# RECEIVER_IC.net
KiCad netlist of a schematic drawn in Altium Designer
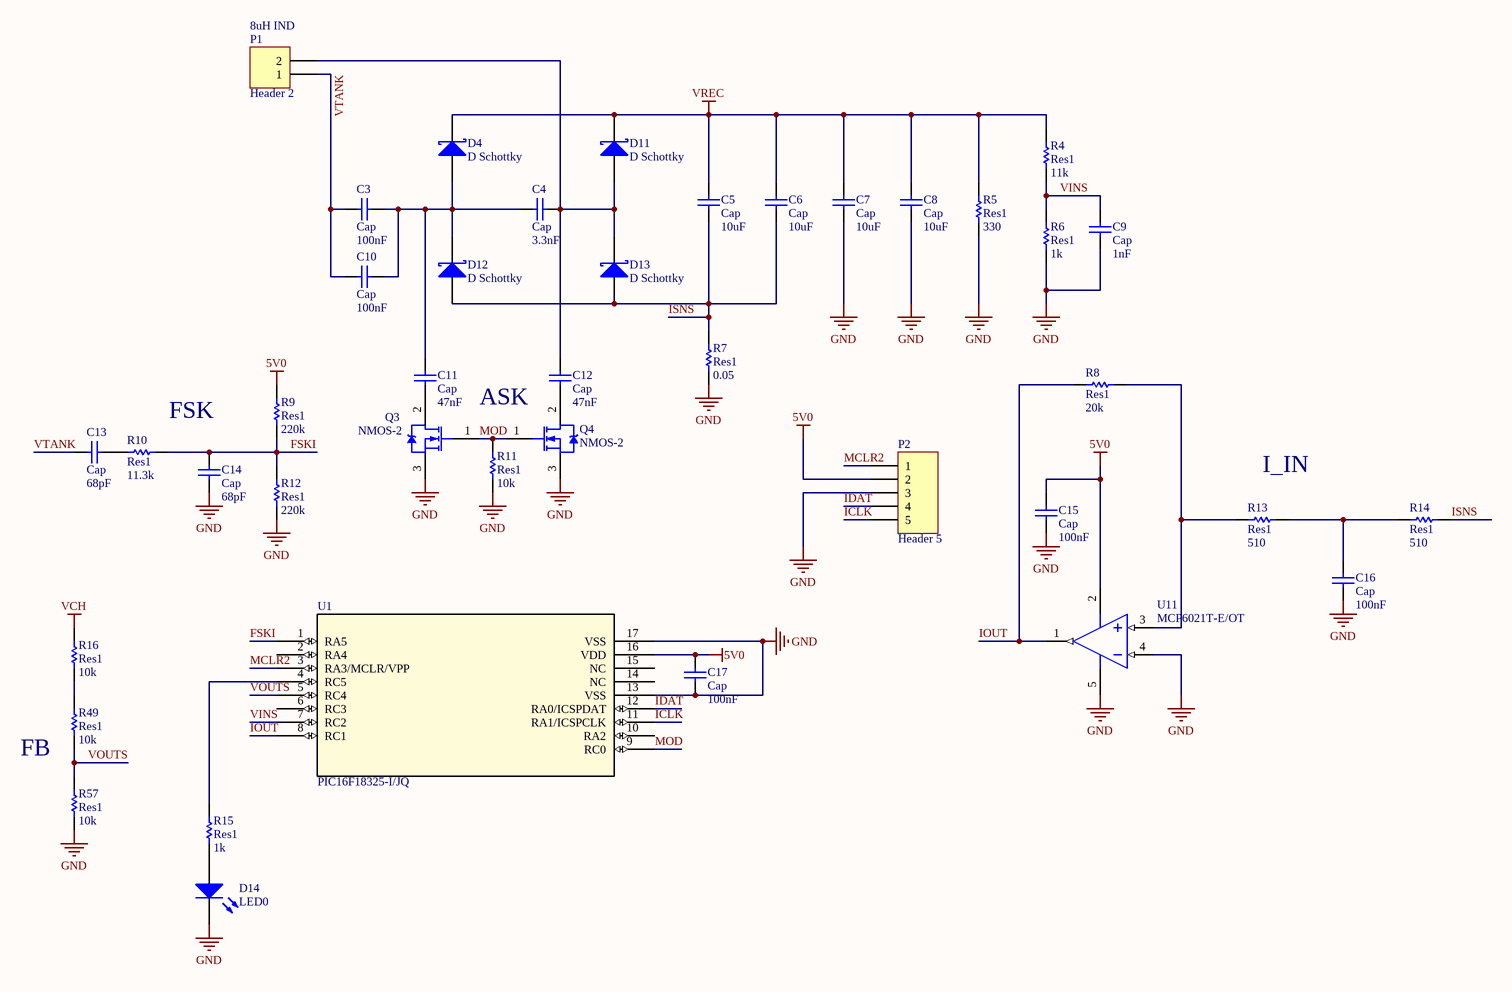
[diagram p0: RECEIVER IC.SchDoc]

(export (version "E")
  (design (tool "Eeschema 10.0.6"))
  (components
    (comp (ref "C3")
      (value "Cap")
      (footprint "C1206")
      (description "Capacitor")
      (fields (field (name "ALTIUM_VALUE") "100nF") (field (name "PUBLISHER") "Altium Limited"))
      (libsource (lib "Miscellaneous Devices") (part "Cap"))
    )
    (comp (ref "C4")
      (value "Cap")
      (footprint "6-0805_M")
      (description "Capacitor")
      (fields (field (name "ALTIUM_VALUE") "3.3nF") (field (name "PUBLISHER") "Altium Limited"))
      (libsource (lib "Miscellaneous Devices") (part "Cap"))
    )
    (comp (ref "C5")
      (value "Cap")
      (footprint "C1210")
      (description "Capacitor")
      (fields (field (name "ALTIUM_VALUE") "10uF") (field (name "PUBLISHER") "Altium Limited"))
      (libsource (lib "Miscellaneous Devices") (part "Cap"))
    )
    (comp (ref "C6")
      (value "Cap")
      (footprint "C1210")
      (description "Capacitor")
      (fields (field (name "ALTIUM_VALUE") "10uF") (field (name "PUBLISHER") "Altium Limited"))
      (libsource (lib "Miscellaneous Devices") (part "Cap"))
    )
    (comp (ref "C7")
      (value "Cap")
      (footprint "C1210")
      (description "Capacitor")
      (fields (field (name "ALTIUM_VALUE") "10uF") (field (name "PUBLISHER") "Altium Limited"))
      (libsource (lib "Miscellaneous Devices") (part "Cap"))
    )
    (comp (ref "C8")
      (value "Cap")
      (footprint "C1210")
      (description "Capacitor")
      (fields (field (name "ALTIUM_VALUE") "10uF") (field (name "PUBLISHER") "Altium Limited"))
      (libsource (lib "Miscellaneous Devices") (part "Cap"))
    )
    (comp (ref "C9")
      (value "Cap")
      (footprint "1608[0603]")
      (description "Capacitor")
      (fields (field (name "ALTIUM_VALUE") "1nF") (field (name "PUBLISHER") "Altium Limited"))
      (libsource (lib "Miscellaneous Devices") (part "Cap"))
    )
    (comp (ref "C10")
      (value "Cap")
      (footprint "C1206")
      (description "Capacitor")
      (fields (field (name "ALTIUM_VALUE") "100nF") (field (name "PUBLISHER") "Altium Limited"))
      (libsource (lib "Miscellaneous Devices") (part "Cap"))
    )
    (comp (ref "C11")
      (value "Cap")
      (footprint "6-0805_M")
      (description "Capacitor")
      (fields (field (name "ALTIUM_VALUE") "47nF") (field (name "PUBLISHER") "Altium Limited"))
      (libsource (lib "Miscellaneous Devices") (part "Cap"))
    )
    (comp (ref "C12")
      (value "Cap")
      (footprint "6-0805_M")
      (description "Capacitor")
      (fields (field (name "ALTIUM_VALUE") "47nF") (field (name "PUBLISHER") "Altium Limited"))
      (libsource (lib "Miscellaneous Devices") (part "Cap"))
    )
    (comp (ref "C13")
      (value "Cap")
      (footprint "1608[0603]")
      (description "Capacitor")
      (fields (field (name "ALTIUM_VALUE") "68pF") (field (name "PUBLISHER") "Altium Limited"))
      (libsource (lib "Miscellaneous Devices") (part "Cap"))
    )
    (comp (ref "C14")
      (value "Cap")
      (footprint "1608[0603]")
      (description "Capacitor")
      (fields (field (name "ALTIUM_VALUE") "68pF") (field (name "PUBLISHER") "Altium Limited"))
      (libsource (lib "Miscellaneous Devices") (part "Cap"))
    )
    (comp (ref "C15")
      (value "Cap")
      (footprint "1608[0603]")
      (description "Capacitor")
      (fields (field (name "ALTIUM_VALUE") "100nF") (field (name "PUBLISHER") "Altium Limited"))
      (libsource (lib "Miscellaneous Devices") (part "Cap"))
    )
    (comp (ref "C16")
      (value "Cap")
      (footprint "1608[0603]")
      (description "Capacitor")
      (fields (field (name "ALTIUM_VALUE") "100nF") (field (name "PUBLISHER") "Altium Limited"))
      (libsource (lib "Miscellaneous Devices") (part "Cap"))
    )
    (comp (ref "C17")
      (value "Cap")
      (footprint "1608[0603]")
      (description "Capacitor")
      (fields (field (name "ALTIUM_VALUE") "100nF") (field (name "PUBLISHER") "Altium Limited"))
      (libsource (lib "Miscellaneous Devices") (part "Cap"))
    )
    (comp (ref "D4")
      (value "D Schottky")
      (footprint "DIO_RB050LAM_ROM")
      (description "Schottky Diode")
      (fields (field (name "PUBLISHER") "Altium Limited"))
      (libsource (lib "Miscellaneous Devices") (part "D Schottky"))
    )
    (comp (ref "D11")
      (value "D Schottky")
      (footprint "DIO_RB050LAM_ROM")
      (description "Schottky Diode")
      (fields (field (name "PUBLISHER") "Altium Limited"))
      (libsource (lib "Miscellaneous Devices") (part "D Schottky"))
    )
    (comp (ref "D12")
      (value "D Schottky")
      (footprint "DIO_RB050LAM_ROM")
      (description "Schottky Diode")
      (fields (field (name "PUBLISHER") "Altium Limited"))
      (libsource (lib "Miscellaneous Devices") (part "D Schottky"))
    )
    (comp (ref "D13")
      (value "D Schottky")
      (footprint "DIO_RB050LAM_ROM")
      (description "Schottky Diode")
      (fields (field (name "PUBLISHER") "Altium Limited"))
      (libsource (lib "Miscellaneous Devices") (part "D Schottky"))
    )
    (comp (ref "D14")
      (value "LED0")
      (footprint "1608[0603]")
      (description "Typical INFRARED GaAs LED")
      (fields (field (name "PUBLISHER") "Altium Limited"))
      (libsource (lib "Miscellaneous Devices") (part "LED0"))
    )
    (comp (ref "P1")
      (value "Header 2")
      (footprint "2-1445096-2")
      (description "Header, 2-Pin")
      (fields (field (name "PUBLISHER") "Altium Limited"))
      (libsource (lib "Miscellaneous Connectors") (part "Header 2"))
    )
    (comp (ref "P2")
      (value "Header 5")
      (footprint "HDR1X5")
      (description "Header, 5-Pin")
      (fields (field (name "PUBLISHER") "Altium Limited"))
      (libsource (lib "Miscellaneous Connectors") (part "Header 5"))
    )
    (comp (ref "Q3")
      (value "NMOS-2")
      (footprint "SOT-23_M")
      (description "N-Channel Power MOSFET")
      (fields (field (name "PUBLISHER") "Altium Limited"))
      (libsource (lib "Miscellaneous Devices") (part "NMOS-2"))
    )
    (comp (ref "Q4")
      (value "NMOS-2")
      (footprint "SOT-23_M")
      (description "N-Channel Power MOSFET")
      (fields (field (name "PUBLISHER") "Altium Limited"))
      (libsource (lib "Miscellaneous Devices") (part "NMOS-2"))
    )
    (comp (ref "R4")
      (value "Res1")
      (footprint "1608[0603]")
      (description "Resistor")
      (fields (field (name "ALTIUM_VALUE") "11k") (field (name "PUBLISHER") "Altium Limited"))
      (libsource (lib "Miscellaneous Devices") (part "Res1"))
    )
    (comp (ref "R5")
      (value "Res1")
      (footprint "C1206")
      (description "Resistor")
      (fields (field (name "ALTIUM_VALUE") "330") (field (name "PUBLISHER") "Altium Limited"))
      (libsource (lib "Miscellaneous Devices") (part "Res1"))
    )
    (comp (ref "R6")
      (value "Res1")
      (footprint "1608[0603]")
      (description "Resistor")
      (fields (field (name "ALTIUM_VALUE") "1k") (field (name "PUBLISHER") "Altium Limited"))
      (libsource (lib "Miscellaneous Devices") (part "Res1"))
    )
    (comp (ref "R7")
      (value "Res1")
      (footprint "C1206")
      (description "Resistor")
      (fields (field (name "ALTIUM_VALUE") "0.05") (field (name "PUBLISHER") "Altium Limited"))
      (libsource (lib "Miscellaneous Devices") (part "Res1"))
    )
    (comp (ref "R8")
      (value "Res1")
      (footprint "1608[0603]")
      (description "Resistor")
      (fields (field (name "ALTIUM_VALUE") "20k") (field (name "PUBLISHER") "Altium Limited"))
      (libsource (lib "Miscellaneous Devices") (part "Res1"))
    )
    (comp (ref "R9")
      (value "Res1")
      (footprint "1608[0603]")
      (description "Resistor")
      (fields (field (name "ALTIUM_VALUE") "220k") (field (name "PUBLISHER") "Altium Limited"))
      (libsource (lib "Miscellaneous Devices") (part "Res1"))
    )
    (comp (ref "R10")
      (value "Res1")
      (footprint "1608[0603]")
      (description "Resistor")
      (fields (field (name "ALTIUM_VALUE") "11.3k") (field (name "PUBLISHER") "Altium Limited"))
      (libsource (lib "Miscellaneous Devices") (part "Res1"))
    )
    (comp (ref "R11")
      (value "Res1")
      (footprint "1608[0603]")
      (description "Resistor")
      (fields (field (name "ALTIUM_VALUE") "10k") (field (name "PUBLISHER") "Altium Limited"))
      (libsource (lib "Miscellaneous Devices") (part "Res1"))
    )
    (comp (ref "R12")
      (value "Res1")
      (footprint "1608[0603]")
      (description "Resistor")
      (fields (field (name "ALTIUM_VALUE") "220k") (field (name "PUBLISHER") "Altium Limited"))
      (libsource (lib "Miscellaneous Devices") (part "Res1"))
    )
    (comp (ref "R13")
      (value "Res1")
      (footprint "1608[0603]")
      (description "Resistor")
      (fields (field (name "ALTIUM_VALUE") "510") (field (name "PUBLISHER") "Altium Limited"))
      (libsource (lib "Miscellaneous Devices") (part "Res1"))
    )
    (comp (ref "R14")
      (value "Res1")
      (footprint "1608[0603]")
      (description "Resistor")
      (fields (field (name "ALTIUM_VALUE") "510") (field (name "PUBLISHER") "Altium Limited"))
      (libsource (lib "Miscellaneous Devices") (part "Res1"))
    )
    (comp (ref "R15")
      (value "Res1")
      (footprint "1608[0603]")
      (description "Resistor")
      (fields (field (name "ALTIUM_VALUE") "1k") (field (name "PUBLISHER") "Altium Limited"))
      (libsource (lib "Miscellaneous Devices") (part "Res1"))
    )
    (comp (ref "R16")
      (value "Res1")
      (footprint "1608[0603]")
      (description "Resistor")
      (fields (field (name "ALTIUM_VALUE") "10k") (field (name "PUBLISHER") "Altium Limited"))
      (libsource (lib "Miscellaneous Devices") (part "Res1"))
    )
    (comp (ref "R49")
      (value "Res1")
      (footprint "1608[0603]")
      (description "Resistor")
      (fields (field (name "ALTIUM_VALUE") "10k") (field (name "PUBLISHER") "Altium Limited"))
      (libsource (lib "Miscellaneous Devices") (part "Res1"))
    )
    (comp (ref "R57")
      (value "Res1")
      (footprint "1608[0603]")
      (description "Resistor")
      (fields (field (name "ALTIUM_VALUE") "10k") (field (name "PUBLISHER") "Altium Limited"))
      (libsource (lib "Miscellaneous Devices") (part "Res1"))
    )
    (comp (ref "U1")
      (value "PIC16F18325-I/JQ")
      (footprint "UQFN16_JQ_MCH")
      (description "No Description Available")
      (fields (field (name "COPYRIGHT") "Copyright (C) 2018 Accelerated Designs. All rights reserved"))
      (libsource (lib "PIC16F18325") (part "PIC16F18325-I/JQ"))
    )
    (comp (ref "U11")
      (value "MCP6021T-E/OT")
      (footprint "SOT-23-OT5_N")
      (libsource (lib "Altium Content Vault") (part "AMP-OPA-MCP6021-SOT5"))
    )
  )
  (nets
    (net (code "1") (name "/FSKI") (class "Default")
      (node (ref "C14") (pin "2") (pinfunction "2_2") (pintype "passive"))
      (node (ref "R10") (pin "2") (pinfunction "2_2") (pintype "passive"))
      (node (ref "R12") (pin "2") (pinfunction "2_2") (pintype "passive"))
      (node (ref "R9") (pin "1") (pinfunction "1_1") (pintype "passive"))
      (node (ref "U1") (pin "1") (pinfunction "RA5_1") (pintype "bidirectional"))
    )
    (net (code "2") (name "/ICLK") (class "Default")
      (node (ref "P2") (pin "5") (pinfunction "5_5") (pintype "passive"))
      (node (ref "U1") (pin "11") (pinfunction "RA1/ICSPCLK_11") (pintype "bidirectional"))
    )
    (net (code "3") (name "/IDAT") (class "Default")
      (node (ref "P2") (pin "4") (pinfunction "4_4") (pintype "passive"))
      (node (ref "U1") (pin "12") (pinfunction "RA0/ICSPDAT_12") (pintype "bidirectional"))
    )
    (net (code "4") (name "/IOUT") (class "Default")
      (node (ref "R8") (pin "1") (pinfunction "1_1") (pintype "passive"))
      (node (ref "U1") (pin "8") (pinfunction "RC1_8") (pintype "bidirectional"))
      (node (ref "U11") (pin "1") (pinfunction "VOUT_1") (pintype "output"))
    )
    (net (code "5") (name "/ISNS") (class "Default")
      (node (ref "C5") (pin "1") (pinfunction "1_1") (pintype "passive"))
      (node (ref "C6") (pin "1") (pinfunction "1_1") (pintype "passive"))
      (node (ref "D12") (pin "1") (pinfunction "A_1") (pintype "passive"))
      (node (ref "D13") (pin "1") (pinfunction "A_1") (pintype "passive"))
      (node (ref "R14") (pin "2") (pinfunction "2_2") (pintype "passive"))
      (node (ref "R7") (pin "2") (pinfunction "2_2") (pintype "passive"))
    )
    (net (code "6") (name "/MCLR2") (class "Default")
      (node (ref "P2") (pin "1") (pinfunction "1_1") (pintype "passive"))
      (node (ref "U1") (pin "3") (pinfunction "RA3/MCLR/VPP_3") (pintype "bidirectional"))
    )
    (net (code "7") (name "/MOD") (class "Default")
      (node (ref "Q3") (pin "1") (pinfunction "G_1") (pintype "passive"))
      (node (ref "Q4") (pin "1") (pinfunction "G_1") (pintype "passive"))
      (node (ref "R11") (pin "2") (pinfunction "2_2") (pintype "passive"))
      (node (ref "U1") (pin "9") (pinfunction "RC0_9") (pintype "bidirectional"))
    )
    (net (code "8") (name "/VINS") (class "Default")
      (node (ref "C9") (pin "2") (pinfunction "2_2") (pintype "passive"))
      (node (ref "R4") (pin "1") (pinfunction "1_1") (pintype "passive"))
      (node (ref "R6") (pin "2") (pinfunction "2_2") (pintype "passive"))
      (node (ref "U1") (pin "7") (pinfunction "RC2_7") (pintype "bidirectional"))
    )
    (net (code "9") (name "/VOUTS") (class "Default")
      (node (ref "R49") (pin "1") (pinfunction "1_1") (pintype "passive"))
      (node (ref "R57") (pin "2") (pinfunction "2_2") (pintype "passive"))
      (node (ref "U1") (pin "5") (pinfunction "RC4_5") (pintype "bidirectional"))
    )
    (net (code "10") (name "/VTANK") (class "Default")
      (node (ref "C10") (pin "1") (pinfunction "1_1") (pintype "passive"))
      (node (ref "C13") (pin "1") (pinfunction "1_1") (pintype "passive"))
      (node (ref "C3") (pin "1") (pinfunction "1_1") (pintype "passive"))
      (node (ref "P1") (pin "1") (pinfunction "1_1") (pintype "passive"))
    )
    (net (code "11") (name "5V0") (class "Default")
      (node (ref "C15") (pin "2") (pinfunction "2_2") (pintype "passive"))
      (node (ref "C17") (pin "2") (pinfunction "2_2") (pintype "passive"))
      (node (ref "P2") (pin "2") (pinfunction "2_2") (pintype "passive"))
      (node (ref "R9") (pin "2") (pinfunction "2_2") (pintype "passive"))
      (node (ref "U1") (pin "16") (pinfunction "VDD_16") (pintype "power_in"))
      (node (ref "U11") (pin "2") (pinfunction "VSS_2") (pintype "power_in"))
    )
    (net (code "12") (name "GND") (class "Default")
      (node (ref "C14") (pin "1") (pinfunction "1_1") (pintype "passive"))
      (node (ref "C15") (pin "1") (pinfunction "1_1") (pintype "passive"))
      (node (ref "C16") (pin "1") (pinfunction "1_1") (pintype "passive"))
      (node (ref "C17") (pin "1") (pinfunction "1_1") (pintype "passive"))
      (node (ref "C7") (pin "1") (pinfunction "1_1") (pintype "passive"))
      (node (ref "C8") (pin "1") (pinfunction "1_1") (pintype "passive"))
      (node (ref "C9") (pin "1") (pinfunction "1_1") (pintype "passive"))
      (node (ref "D14") (pin "2") (pinfunction "K_2") (pintype "passive"))
      (node (ref "P2") (pin "3") (pinfunction "3_3") (pintype "passive"))
      (node (ref "Q3") (pin "3") (pinfunction "S_3") (pintype "passive"))
      (node (ref "Q4") (pin "3") (pinfunction "S_3") (pintype "passive"))
      (node (ref "R11") (pin "1") (pinfunction "1_1") (pintype "passive"))
      (node (ref "R12") (pin "1") (pinfunction "1_1") (pintype "passive"))
      (node (ref "R5") (pin "1") (pinfunction "1_1") (pintype "passive"))
      (node (ref "R57") (pin "1") (pinfunction "1_1") (pintype "passive"))
      (node (ref "R6") (pin "1") (pinfunction "1_1") (pintype "passive"))
      (node (ref "R7") (pin "1") (pinfunction "1_1") (pintype "passive"))
      (node (ref "U1") (pin "13") (pinfunction "VSS_13") (pintype "passive"))
      (node (ref "U1") (pin "17") (pinfunction "VSS_17") (pintype "passive"))
      (node (ref "U11") (pin "4") (pinfunction "VIN-_4") (pintype "input"))
      (node (ref "U11") (pin "5") (pinfunction "VDD_5") (pintype "power_in"))
    )
    (net (code "13") (name "Net-(C13-Pad2)") (class "Default")
      (node (ref "C13") (pin "2") (pinfunction "2_2") (pintype "passive"))
      (node (ref "R10") (pin "1") (pinfunction "1_1") (pintype "passive"))
    )
    (net (code "14") (name "Net-(C16-Pad2)") (class "Default")
      (node (ref "C16") (pin "2") (pinfunction "2_2") (pintype "passive"))
      (node (ref "R13") (pin "2") (pinfunction "2_2") (pintype "passive"))
      (node (ref "R14") (pin "1") (pinfunction "1_1") (pintype "passive"))
    )
    (net (code "15") (name "Net-(D11-A)") (class "Default")
      (node (ref "C12") (pin "2") (pinfunction "2_2") (pintype "passive"))
      (node (ref "C4") (pin "2") (pinfunction "2_2") (pintype "passive"))
      (node (ref "D11") (pin "1") (pinfunction "A_1") (pintype "passive"))
      (node (ref "D13") (pin "2") (pinfunction "K_2") (pintype "passive"))
      (node (ref "P1") (pin "2") (pinfunction "2_2") (pintype "passive"))
    )
    (net (code "16") (name "Net-(D12-K)") (class "Default")
      (node (ref "C10") (pin "2") (pinfunction "2_2") (pintype "passive"))
      (node (ref "C11") (pin "2") (pinfunction "2_2") (pintype "passive"))
      (node (ref "C3") (pin "2") (pinfunction "2_2") (pintype "passive"))
      (node (ref "C4") (pin "1") (pinfunction "1_1") (pintype "passive"))
      (node (ref "D12") (pin "2") (pinfunction "K_2") (pintype "passive"))
      (node (ref "D4") (pin "1") (pinfunction "A_1") (pintype "passive"))
    )
    (net (code "17") (name "Net-(D14-A)") (class "Default")
      (node (ref "D14") (pin "1") (pinfunction "A_1") (pintype "passive"))
      (node (ref "R15") (pin "1") (pinfunction "1_1") (pintype "passive"))
    )
    (net (code "18") (name "Net-(Q3-D)") (class "Default")
      (node (ref "C11") (pin "1") (pinfunction "1_1") (pintype "passive"))
      (node (ref "Q3") (pin "2") (pinfunction "D_2") (pintype "passive"))
    )
    (net (code "19") (name "Net-(Q4-D)") (class "Default")
      (node (ref "C12") (pin "1") (pinfunction "1_1") (pintype "passive"))
      (node (ref "Q4") (pin "2") (pinfunction "D_2") (pintype "passive"))
    )
    (net (code "20") (name "Net-(R16-Pad1)") (class "Default")
      (node (ref "R16") (pin "1") (pinfunction "1_1") (pintype "passive"))
      (node (ref "R49") (pin "2") (pinfunction "2_2") (pintype "passive"))
    )
    (net (code "21") (name "Net-(U1-RC5)") (class "Default")
      (node (ref "R15") (pin "2") (pinfunction "2_2") (pintype "passive"))
      (node (ref "U1") (pin "4") (pinfunction "RC5_4") (pintype "bidirectional"))
    )
    (net (code "22") (name "Net-(U11-VIN+)") (class "Default")
      (node (ref "R13") (pin "1") (pinfunction "1_1") (pintype "passive"))
      (node (ref "R8") (pin "2") (pinfunction "2_2") (pintype "passive"))
      (node (ref "U11") (pin "3") (pinfunction "VIN+_3") (pintype "input"))
    )
    (net (code "23") (name "VCH") (class "Default")
      (node (ref "R16") (pin "2") (pinfunction "2_2") (pintype "passive"))
    )
    (net (code "24") (name "VREC") (class "Default")
      (node (ref "C5") (pin "2") (pinfunction "2_2") (pintype "passive"))
      (node (ref "C6") (pin "2") (pinfunction "2_2") (pintype "passive"))
      (node (ref "C7") (pin "2") (pinfunction "2_2") (pintype "passive"))
      (node (ref "C8") (pin "2") (pinfunction "2_2") (pintype "passive"))
      (node (ref "D11") (pin "2") (pinfunction "K_2") (pintype "passive"))
      (node (ref "D4") (pin "2") (pinfunction "K_2") (pintype "passive"))
      (node (ref "R4") (pin "2") (pinfunction "2_2") (pintype "passive"))
      (node (ref "R5") (pin "2") (pinfunction "2_2") (pintype "passive"))
    )
    (net (code "25") (name "unconnected-(U1-NC-Pad14)") (class "Default")
      (node (ref "U1") (pin "14") (pinfunction "NC_14") (pintype "passive"))
    )
    (net (code "26") (name "unconnected-(U1-NC-Pad15)") (class "Default")
      (node (ref "U1") (pin "15") (pinfunction "NC_15") (pintype "passive"))
    )
    (net (code "27") (name "unconnected-(U1-RA2-Pad10)") (class "Default")
      (node (ref "U1") (pin "10") (pinfunction "RA2_10") (pintype "bidirectional"))
    )
    (net (code "28") (name "unconnected-(U1-RA4-Pad2)") (class "Default")
      (node (ref "U1") (pin "2") (pinfunction "RA4_2") (pintype "bidirectional"))
    )
    (net (code "29") (name "unconnected-(U1-RC3-Pad6)") (class "Default")
      (node (ref "U1") (pin "6") (pinfunction "RC3_6") (pintype "bidirectional"))
    )
  )
)
